# dcc-promini.net
KiCad netlist of a schematic drawn in EAGLE
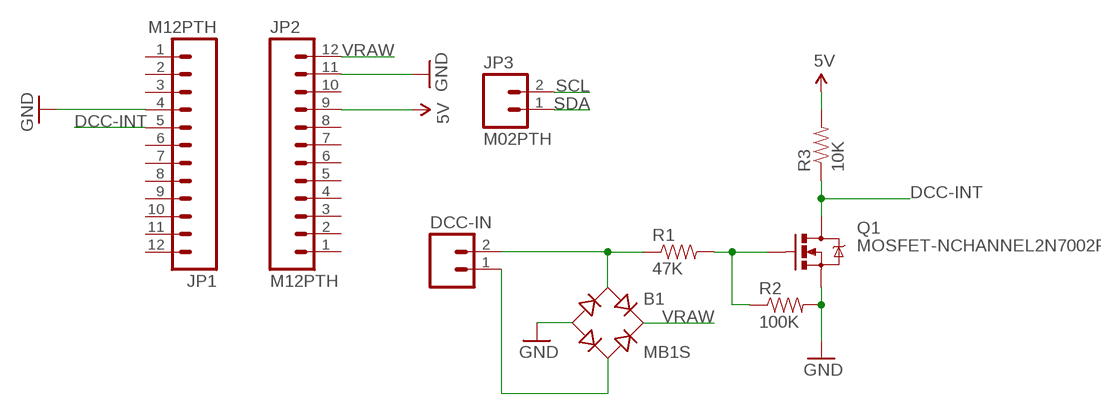
[diagram p0: schematic, sheet 1]

(export (version "E")
  (design (tool "Eeschema 10.0.6"))
  (components
    (comp (ref "B1")
      (value "MB1S")
      (footprint "eagle-import:SOIC-4")
      (libsource (lib "eagle-import") (part "MBS1"))
    )
    (comp (ref "DCC-IN")
      (value "M02-JST-2-PTH-NO_SILK")
      (footprint "eagle-import:JST-2-PTH-NS")
      (libsource (lib "eagle-import") (part "M02-JST-2-PTH-NO_SILK"))
    )
    (comp (ref "JP1")
      (value "M12PTH")
      (footprint "eagle-import:1X12")
      (libsource (lib "eagle-import") (part "M12PTH"))
    )
    (comp (ref "JP2")
      (value "M12PTH")
      (footprint "eagle-import:1X12")
      (libsource (lib "eagle-import") (part "M12PTH"))
    )
    (comp (ref "JP3")
      (value "M02PTH")
      (footprint "eagle-import:1X02")
      (libsource (lib "eagle-import") (part "M02PTH"))
    )
    (comp (ref "Q1")
      (value "MOSFET-NCHANNEL2N7002PW")
      (footprint "eagle-import:SOT323")
      (libsource (lib "eagle-import") (part "MOSFET-NCHANNEL2N7002PW"))
    )
    (comp (ref "R1")
      (value "47K")
      (footprint "eagle-import:0603-RES")
      (libsource (lib "eagle-import") (part "RESISTOR0603-RES"))
    )
    (comp (ref "R2")
      (value "100K")
      (footprint "eagle-import:0603-RES")
      (libsource (lib "eagle-import") (part "RESISTOR0603-RES"))
    )
    (comp (ref "R3")
      (value "10K")
      (footprint "eagle-import:0603-RES")
      (libsource (lib "eagle-import") (part "RESISTOR0603-RES"))
    )
  )
  (nets
    (net (code "1") (name "/DCC-INT") (class "Default")
      (node (ref "JP1") (pin "5") (pinfunction "5_5") (pintype "passive"))
      (node (ref "Q1") (pin "3") (pinfunction "D_3") (pintype "passive"))
      (node (ref "R3") (pin "1") (pinfunction "1_1") (pintype "passive"))
    )
    (net (code "2") (name "/SCL") (class "Default")
      (node (ref "JP3") (pin "2") (pinfunction "2_2") (pintype "passive"))
    )
    (net (code "3") (name "/SDA") (class "Default")
      (node (ref "JP3") (pin "1") (pinfunction "1_1") (pintype "passive"))
    )
    (net (code "4") (name "/VRAW") (class "Default")
      (node (ref "B1") (pin "+") (pinfunction "+_+") (pintype "passive"))
      (node (ref "JP2") (pin "12") (pinfunction "12_12") (pintype "passive"))
    )
    (net (code "5") (name "5V") (class "Default")
      (node (ref "JP2") (pin "9") (pinfunction "9_9") (pintype "passive"))
      (node (ref "R3") (pin "2") (pinfunction "2_2") (pintype "passive"))
    )
    (net (code "6") (name "GND") (class "Default")
      (node (ref "B1") (pin "-") (pinfunction "-_-") (pintype "passive"))
      (node (ref "JP1") (pin "4") (pinfunction "4_4") (pintype "passive"))
      (node (ref "JP2") (pin "11") (pinfunction "11_11") (pintype "passive"))
      (node (ref "Q1") (pin "2") (pinfunction "S_2") (pintype "passive"))
      (node (ref "R2") (pin "2") (pinfunction "2_2") (pintype "passive"))
    )
    (net (code "7") (name "Net-(B1-AC1)") (class "Default")
      (node (ref "B1") (pin "~1") (pinfunction "AC1_~1") (pintype "passive"))
      (node (ref "DCC-IN") (pin "2") (pinfunction "2_2") (pintype "passive"))
      (node (ref "R1") (pin "1") (pinfunction "1_1") (pintype "passive"))
    )
    (net (code "8") (name "Net-(B1-AC2)") (class "Default")
      (node (ref "B1") (pin "~2") (pinfunction "AC2_~2") (pintype "passive"))
      (node (ref "DCC-IN") (pin "1") (pinfunction "1_1") (pintype "passive"))
    )
    (net (code "9") (name "Net-(Q1-G)") (class "Default")
      (node (ref "Q1") (pin "1") (pinfunction "G_1") (pintype "passive"))
      (node (ref "R1") (pin "2") (pinfunction "2_2") (pintype "passive"))
      (node (ref "R2") (pin "1") (pinfunction "1_1") (pintype "passive"))
    )
    (net (code "10") (name "unconnected-(JP1-Pad1)") (class "Default")
      (node (ref "JP1") (pin "1") (pinfunction "1_1") (pintype "passive"))
    )
    (net (code "11") (name "unconnected-(JP1-Pad2)") (class "Default")
      (node (ref "JP1") (pin "2") (pinfunction "2_2") (pintype "passive"))
    )
    (net (code "12") (name "unconnected-(JP1-Pad3)") (class "Default")
      (node (ref "JP1") (pin "3") (pinfunction "3_3") (pintype "passive"))
    )
    (net (code "13") (name "unconnected-(JP1-Pad6)") (class "Default")
      (node (ref "JP1") (pin "6") (pinfunction "6_6") (pintype "passive"))
    )
    (net (code "14") (name "unconnected-(JP1-Pad7)") (class "Default")
      (node (ref "JP1") (pin "7") (pinfunction "7_7") (pintype "passive"))
    )
    (net (code "15") (name "unconnected-(JP1-Pad8)") (class "Default")
      (node (ref "JP1") (pin "8") (pinfunction "8_8") (pintype "passive"))
    )
    (net (code "16") (name "unconnected-(JP1-Pad9)") (class "Default")
      (node (ref "JP1") (pin "9") (pinfunction "9_9") (pintype "passive"))
    )
    (net (code "17") (name "unconnected-(JP1-Pad10)") (class "Default")
      (node (ref "JP1") (pin "10") (pinfunction "10_10") (pintype "passive"))
    )
    (net (code "18") (name "unconnected-(JP1-Pad11)") (class "Default")
      (node (ref "JP1") (pin "11") (pinfunction "11_11") (pintype "passive"))
    )
    (net (code "19") (name "unconnected-(JP1-Pad12)") (class "Default")
      (node (ref "JP1") (pin "12") (pinfunction "12_12") (pintype "passive"))
    )
    (net (code "20") (name "unconnected-(JP2-Pad1)") (class "Default")
      (node (ref "JP2") (pin "1") (pinfunction "1_1") (pintype "passive"))
    )
    (net (code "21") (name "unconnected-(JP2-Pad2)") (class "Default")
      (node (ref "JP2") (pin "2") (pinfunction "2_2") (pintype "passive"))
    )
    (net (code "22") (name "unconnected-(JP2-Pad3)") (class "Default")
      (node (ref "JP2") (pin "3") (pinfunction "3_3") (pintype "passive"))
    )
    (net (code "23") (name "unconnected-(JP2-Pad4)") (class "Default")
      (node (ref "JP2") (pin "4") (pinfunction "4_4") (pintype "passive"))
    )
    (net (code "24") (name "unconnected-(JP2-Pad5)") (class "Default")
      (node (ref "JP2") (pin "5") (pinfunction "5_5") (pintype "passive"))
    )
    (net (code "25") (name "unconnected-(JP2-Pad6)") (class "Default")
      (node (ref "JP2") (pin "6") (pinfunction "6_6") (pintype "passive"))
    )
    (net (code "26") (name "unconnected-(JP2-Pad7)") (class "Default")
      (node (ref "JP2") (pin "7") (pinfunction "7_7") (pintype "passive"))
    )
    (net (code "27") (name "unconnected-(JP2-Pad8)") (class "Default")
      (node (ref "JP2") (pin "8") (pinfunction "8_8") (pintype "passive"))
    )
    (net (code "28") (name "unconnected-(JP2-Pad10)") (class "Default")
      (node (ref "JP2") (pin "10") (pinfunction "10_10") (pintype "passive"))
    )
  )
)
